# Card.net
KiCad netlist of a schematic drawn in EAGLE
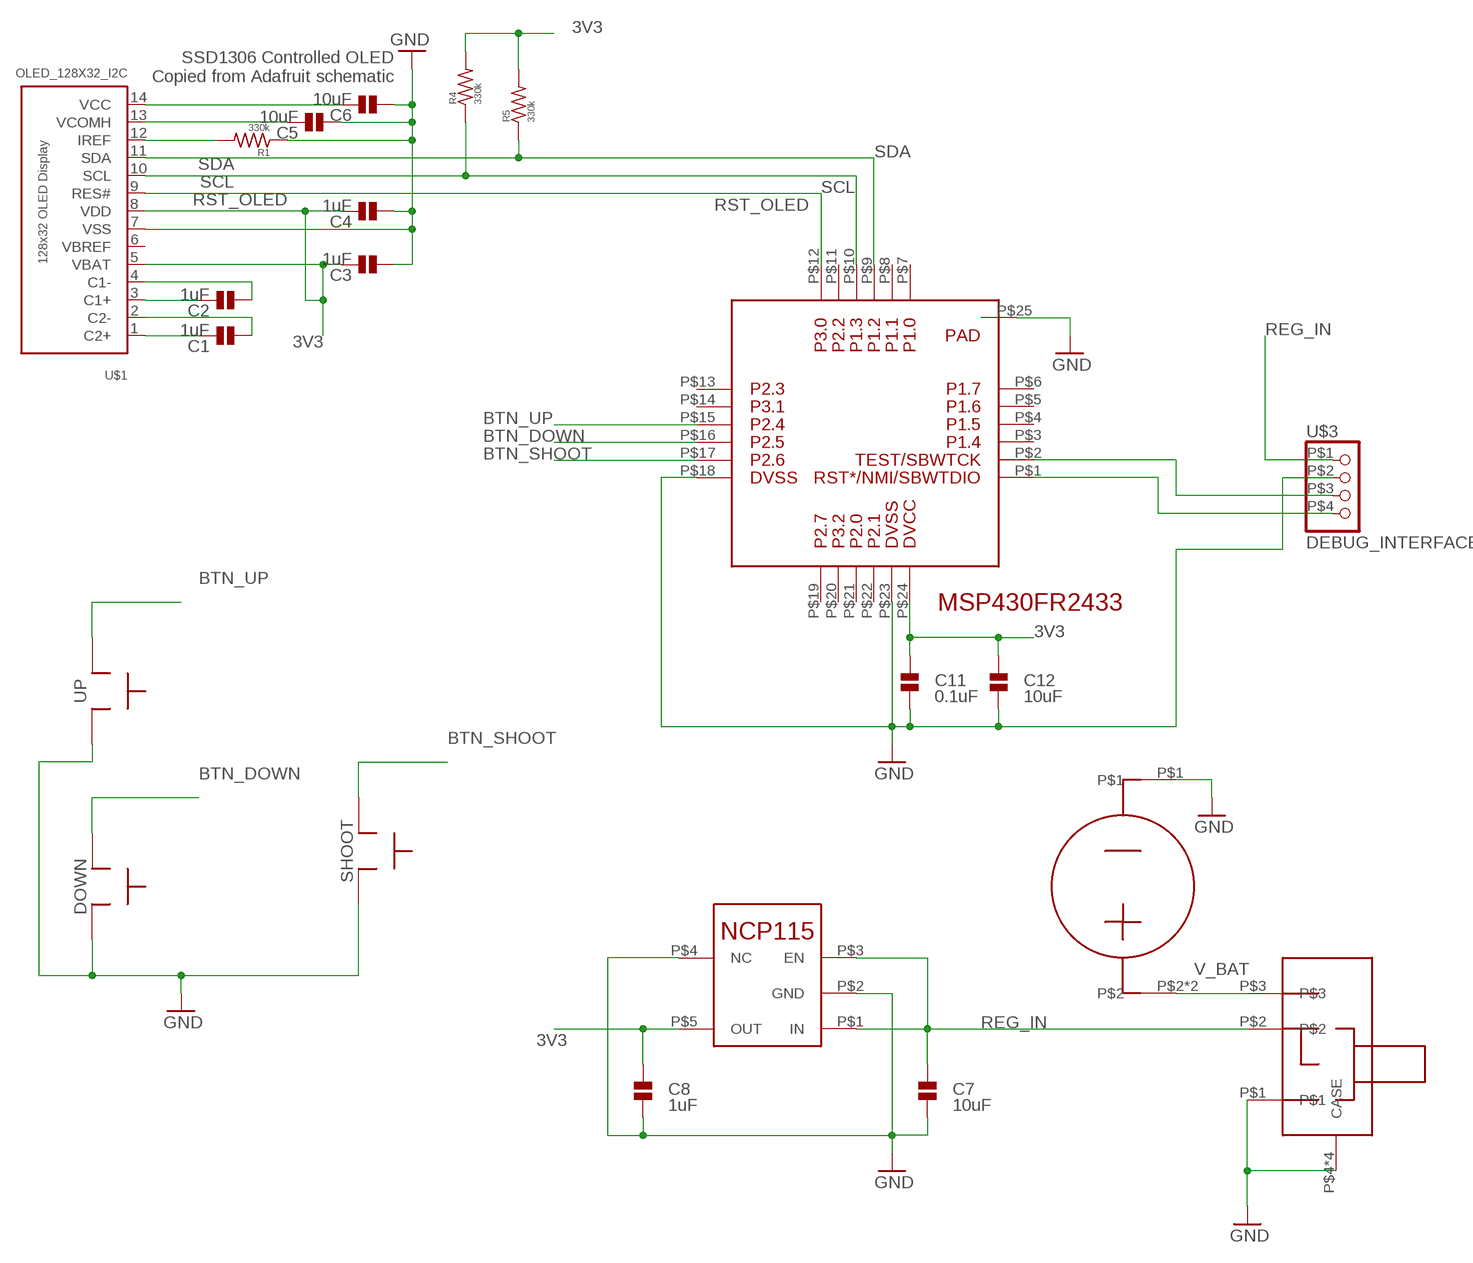
[diagram p0: schematic, sheet 1]

(export (version "E")
  (design (tool "Eeschema 10.0.6"))
  (components
    (comp (ref "C1")
      (value "1uF")
      (footprint "eagle-import:0603")
      (libsource (lib "eagle-import") (part "C-0603"))
    )
    (comp (ref "C2")
      (value "1uF")
      (footprint "eagle-import:0603")
      (libsource (lib "eagle-import") (part "C-0603"))
    )
    (comp (ref "C3")
      (value "1uF")
      (footprint "eagle-import:0603")
      (libsource (lib "eagle-import") (part "C-0603"))
    )
    (comp (ref "C4")
      (value "1uF")
      (footprint "eagle-import:0603")
      (libsource (lib "eagle-import") (part "C-0603"))
    )
    (comp (ref "C5")
      (value "10uF")
      (footprint "eagle-import:0603")
      (libsource (lib "eagle-import") (part "C-0603"))
    )
    (comp (ref "C6")
      (value "10uF")
      (footprint "eagle-import:0603")
      (libsource (lib "eagle-import") (part "C-0603"))
    )
    (comp (ref "C7")
      (value "10uF")
      (footprint "eagle-import:0603")
      (libsource (lib "eagle-import") (part "C-0603"))
    )
    (comp (ref "C8")
      (value "1uF")
      (footprint "eagle-import:0603")
      (libsource (lib "eagle-import") (part "C-0603"))
    )
    (comp (ref "C11")
      (value "0.1uF")
      (footprint "eagle-import:0603")
      (libsource (lib "eagle-import") (part "C-0603"))
    )
    (comp (ref "C12")
      (value "10uF")
      (footprint "eagle-import:0603")
      (libsource (lib "eagle-import") (part "C-0603"))
    )
    (comp (ref "DOWN")
      (value "EVQ-Q2B02W")
      (footprint "eagle-import:EVQQ2")
      (libsource (lib "eagle-import") (part "EVQ-Q2B02W"))
    )
    (comp (ref "R1")
      (value "330k")
      (footprint "eagle-import:0603")
      (libsource (lib "eagle-import") (part "R-0603"))
    )
    (comp (ref "R4")
      (value "330k")
      (footprint "eagle-import:0603")
      (libsource (lib "eagle-import") (part "R-0603"))
    )
    (comp (ref "R5")
      (value "330k")
      (footprint "eagle-import:0603")
      (libsource (lib "eagle-import") (part "R-0603"))
    )
    (comp (ref "SHOOT")
      (value "EVQ-Q2B02W")
      (footprint "eagle-import:EVQQ2")
      (libsource (lib "eagle-import") (part "EVQ-Q2B02W"))
    )
    (comp (ref "U$1")
      (value "OLED_128X32_I2C")
      (footprint "eagle-import:OLED_I2C")
      (libsource (lib "eagle-import") (part "OLED_128X32_I2C"))
    )
    (comp (ref "U$2")
      (value "MSP430FR2433-VQFN")
      (footprint "eagle-import:VQFN-24")
      (libsource (lib "eagle-import") (part "MSP430FR2433-VQFN"))
    )
    (comp (ref "U$3")
      (value "DEBUG_INTERFACE")
      (footprint "eagle-import:DEBUG_INTERFACE_6PIN")
      (libsource (lib "eagle-import") (part "DEBUG_INTERFACE"))
    )
    (comp (ref "U$4")
      (value "BAT-HLD-001")
      (footprint "eagle-import:BAT-HLD-001")
      (libsource (lib "eagle-import") (part "BAT-HLD-001"))
    )
    (comp (ref "U$5")
      (value "CUS-12TB")
      (footprint "eagle-import:CUS-12B")
      (libsource (lib "eagle-import") (part "CUS-12TB"))
    )
    (comp (ref "U$6")
      (value "NCP115")
      (footprint "eagle-import:TSOP-5")
      (libsource (lib "eagle-import") (part "NCP115"))
    )
    (comp (ref "UP")
      (value "EVQ-Q2B02W")
      (footprint "eagle-import:EVQQ2")
      (libsource (lib "eagle-import") (part "EVQ-Q2B02W"))
    )
  )
  (nets
    (net (code "1") (name "/3V3") (class "Default")
      (node (ref "C11") (pin "2") (pinfunction "2_2") (pintype "passive"))
      (node (ref "C12") (pin "2") (pinfunction "2_2") (pintype "passive"))
      (node (ref "C3") (pin "2") (pinfunction "2_2") (pintype "passive"))
      (node (ref "C4") (pin "2") (pinfunction "2_2") (pintype "passive"))
      (node (ref "C8") (pin "2") (pinfunction "2_2") (pintype "passive"))
      (node (ref "R4") (pin "2") (pinfunction "2_2") (pintype "passive"))
      (node (ref "R5") (pin "2") (pinfunction "2_2") (pintype "passive"))
      (node (ref "U$1") (pin "5") (pinfunction "VBAT_5") (pintype "power_in"))
      (node (ref "U$1") (pin "8") (pinfunction "VDD_8") (pintype "power_in"))
      (node (ref "U$2") (pin "P$24") (pinfunction "P$24_P$24") (pintype "bidirectional"))
      (node (ref "U$6") (pin "P$5") (pinfunction "OUT_P$5") (pintype "bidirectional"))
    )
    (net (code "2") (name "/BTN_DOWN") (class "Default")
      (node (ref "DOWN") (pin "P$1_A") (pinfunction "P$1_P$1_A") (pintype "bidirectional"))
      (node (ref "DOWN") (pin "P$2_A") (pinfunction "P$1_P$2_A") (pintype "bidirectional"))
      (node (ref "U$2") (pin "P$16") (pinfunction "P$16_P$16") (pintype "bidirectional"))
    )
    (net (code "3") (name "/BTN_SHOOT") (class "Default")
      (node (ref "SHOOT") (pin "P$1_A") (pinfunction "P$1_P$1_A") (pintype "bidirectional"))
      (node (ref "SHOOT") (pin "P$2_A") (pinfunction "P$1_P$2_A") (pintype "bidirectional"))
      (node (ref "U$2") (pin "P$17") (pinfunction "P$17_P$17") (pintype "bidirectional"))
    )
    (net (code "4") (name "/BTN_UP") (class "Default")
      (node (ref "U$2") (pin "P$15") (pinfunction "P$15_P$15") (pintype "bidirectional"))
      (node (ref "UP") (pin "P$1_A") (pinfunction "P$1_P$1_A") (pintype "bidirectional"))
      (node (ref "UP") (pin "P$2_A") (pinfunction "P$1_P$2_A") (pintype "bidirectional"))
    )
    (net (code "5") (name "/REG_IN") (class "Default")
      (node (ref "C7") (pin "2") (pinfunction "2_2") (pintype "passive"))
      (node (ref "U$3") (pin "P$1") (pinfunction "P$1_P$1") (pintype "passive"))
      (node (ref "U$5") (pin "P$2") (pinfunction "P$2_P$2") (pintype "bidirectional"))
      (node (ref "U$6") (pin "P$1") (pinfunction "IN_P$1") (pintype "bidirectional"))
      (node (ref "U$6") (pin "P$3") (pinfunction "EN_P$3") (pintype "bidirectional"))
    )
    (net (code "6") (name "/RST_OLED") (class "Default")
      (node (ref "U$1") (pin "9") (pinfunction "RES#_9") (pintype "bidirectional"))
      (node (ref "U$2") (pin "P$12") (pinfunction "P$12_P$12") (pintype "bidirectional"))
    )
    (net (code "7") (name "/SCL") (class "Default")
      (node (ref "R4") (pin "1") (pinfunction "1_1") (pintype "passive"))
      (node (ref "U$1") (pin "10") (pinfunction "SCL_10") (pintype "bidirectional"))
      (node (ref "U$2") (pin "P$10") (pinfunction "P$10_P$10") (pintype "bidirectional"))
    )
    (net (code "8") (name "/SDA") (class "Default")
      (node (ref "R5") (pin "1") (pinfunction "1_1") (pintype "passive"))
      (node (ref "U$1") (pin "11") (pinfunction "SDA_11") (pintype "bidirectional"))
      (node (ref "U$2") (pin "P$9") (pinfunction "P$9_P$9") (pintype "bidirectional"))
    )
    (net (code "9") (name "/VBREF") (class "Default")
      (node (ref "U$1") (pin "6") (pinfunction "VBREF_6") (pintype "power_in"))
    )
    (net (code "10") (name "/V_BAT") (class "Default")
      (node (ref "U$4") (pin "P$2") (pinfunction "P$2_P$2") (pintype "bidirectional"))
      (node (ref "U$4") (pin "P$3") (pinfunction "P$2_P$3") (pintype "bidirectional"))
      (node (ref "U$5") (pin "P$3") (pinfunction "P$3_P$3") (pintype "bidirectional"))
    )
    (net (code "11") (name "GND") (class "Default")
      (node (ref "C11") (pin "1") (pinfunction "1_1") (pintype "passive"))
      (node (ref "C12") (pin "1") (pinfunction "1_1") (pintype "passive"))
      (node (ref "C3") (pin "1") (pinfunction "1_1") (pintype "passive"))
      (node (ref "C4") (pin "1") (pinfunction "1_1") (pintype "passive"))
      (node (ref "C5") (pin "1") (pinfunction "1_1") (pintype "passive"))
      (node (ref "C6") (pin "1") (pinfunction "1_1") (pintype "passive"))
      (node (ref "C7") (pin "1") (pinfunction "1_1") (pintype "passive"))
      (node (ref "C8") (pin "1") (pinfunction "1_1") (pintype "passive"))
      (node (ref "DOWN") (pin "P$3_B") (pinfunction "P$2_P$3_B") (pintype "bidirectional"))
      (node (ref "DOWN") (pin "P$4_B") (pinfunction "P$2_P$4_B") (pintype "bidirectional"))
      (node (ref "R1") (pin "1") (pinfunction "1_1") (pintype "passive"))
      (node (ref "SHOOT") (pin "P$3_B") (pinfunction "P$2_P$3_B") (pintype "bidirectional"))
      (node (ref "SHOOT") (pin "P$4_B") (pinfunction "P$2_P$4_B") (pintype "bidirectional"))
      (node (ref "U$1") (pin "7") (pinfunction "VSS_7") (pintype "power_in"))
      (node (ref "U$2") (pin "P$18") (pinfunction "P$18_P$18") (pintype "bidirectional"))
      (node (ref "U$2") (pin "P$23") (pinfunction "P$23_P$23") (pintype "bidirectional"))
      (node (ref "U$2") (pin "P$25") (pinfunction "P$25_P$25") (pintype "bidirectional"))
      (node (ref "U$3") (pin "P$2") (pinfunction "P$2_P$2") (pintype "passive"))
      (node (ref "U$4") (pin "P$1") (pinfunction "P$1_P$1") (pintype "bidirectional"))
      (node (ref "U$5") (pin "P$1") (pinfunction "P$1_P$1") (pintype "bidirectional"))
      (node (ref "U$5") (pin "P$4") (pinfunction "CASE_P$4") (pintype "bidirectional"))
      (node (ref "U$5") (pin "P$5") (pinfunction "CASE_P$5") (pintype "bidirectional"))
      (node (ref "U$5") (pin "P$6") (pinfunction "CASE_P$6") (pintype "bidirectional"))
      (node (ref "U$5") (pin "P$7") (pinfunction "CASE_P$7") (pintype "bidirectional"))
      (node (ref "U$6") (pin "P$2") (pinfunction "GND_P$2") (pintype "bidirectional"))
      (node (ref "U$6") (pin "P$4") (pinfunction "NC_P$4") (pintype "bidirectional"))
      (node (ref "UP") (pin "P$3_B") (pinfunction "P$2_P$3_B") (pintype "bidirectional"))
      (node (ref "UP") (pin "P$4_B") (pinfunction "P$2_P$4_B") (pintype "bidirectional"))
    )
    (net (code "12") (name "Net-(U$1-C1+)") (class "Default")
      (node (ref "C2") (pin "2") (pinfunction "2_2") (pintype "passive"))
      (node (ref "U$1") (pin "3") (pinfunction "C1+_3") (pintype "bidirectional"))
    )
    (net (code "13") (name "Net-(U$1-C1-)") (class "Default")
      (node (ref "C2") (pin "1") (pinfunction "1_1") (pintype "passive"))
      (node (ref "U$1") (pin "4") (pinfunction "C1-_4") (pintype "bidirectional"))
    )
    (net (code "14") (name "Net-(U$1-C2+)") (class "Default")
      (node (ref "C1") (pin "2") (pinfunction "2_2") (pintype "passive"))
      (node (ref "U$1") (pin "1") (pinfunction "C2+_1") (pintype "bidirectional"))
    )
    (net (code "15") (name "Net-(U$1-C2-)") (class "Default")
      (node (ref "C1") (pin "1") (pinfunction "1_1") (pintype "passive"))
      (node (ref "U$1") (pin "2") (pinfunction "C2-_2") (pintype "bidirectional"))
    )
    (net (code "16") (name "Net-(U$1-IREF)") (class "Default")
      (node (ref "R1") (pin "2") (pinfunction "2_2") (pintype "passive"))
      (node (ref "U$1") (pin "12") (pinfunction "IREF_12") (pintype "bidirectional"))
    )
    (net (code "17") (name "Net-(U$1-VCC)") (class "Default")
      (node (ref "C6") (pin "2") (pinfunction "2_2") (pintype "passive"))
      (node (ref "U$1") (pin "14") (pinfunction "VCC_14") (pintype "power_in"))
    )
    (net (code "18") (name "Net-(U$1-VCOMH)") (class "Default")
      (node (ref "C5") (pin "2") (pinfunction "2_2") (pintype "passive"))
      (node (ref "U$1") (pin "13") (pinfunction "VCOMH_13") (pintype "power_in"))
    )
    (net (code "19") (name "Net-(U$2-PadP$1)") (class "Default")
      (node (ref "U$2") (pin "P$1") (pinfunction "P$1_P$1") (pintype "bidirectional"))
      (node (ref "U$3") (pin "P$4") (pinfunction "P$4_P$4") (pintype "passive"))
    )
    (net (code "20") (name "Net-(U$2-PadP$2)") (class "Default")
      (node (ref "U$2") (pin "P$2") (pinfunction "P$2_P$2") (pintype "bidirectional"))
      (node (ref "U$3") (pin "P$3") (pinfunction "P$3_P$3") (pintype "passive"))
    )
    (net (code "21") (name "unconnected-(U$2-PadP$3)") (class "Default")
      (node (ref "U$2") (pin "P$3") (pinfunction "P$3_P$3") (pintype "bidirectional"))
    )
    (net (code "22") (name "unconnected-(U$2-PadP$4)") (class "Default")
      (node (ref "U$2") (pin "P$4") (pinfunction "P$4_P$4") (pintype "bidirectional"))
    )
    (net (code "23") (name "unconnected-(U$2-PadP$5)") (class "Default")
      (node (ref "U$2") (pin "P$5") (pinfunction "P$5_P$5") (pintype "bidirectional"))
    )
    (net (code "24") (name "unconnected-(U$2-PadP$6)") (class "Default")
      (node (ref "U$2") (pin "P$6") (pinfunction "P$6_P$6") (pintype "bidirectional"))
    )
    (net (code "25") (name "unconnected-(U$2-PadP$7)") (class "Default")
      (node (ref "U$2") (pin "P$7") (pinfunction "P$7_P$7") (pintype "bidirectional"))
    )
    (net (code "26") (name "unconnected-(U$2-PadP$8)") (class "Default")
      (node (ref "U$2") (pin "P$8") (pinfunction "P$8_P$8") (pintype "bidirectional"))
    )
    (net (code "27") (name "unconnected-(U$2-PadP$11)") (class "Default")
      (node (ref "U$2") (pin "P$11") (pinfunction "P$11_P$11") (pintype "bidirectional"))
    )
    (net (code "28") (name "unconnected-(U$2-PadP$13)") (class "Default")
      (node (ref "U$2") (pin "P$13") (pinfunction "P$13_P$13") (pintype "bidirectional"))
    )
    (net (code "29") (name "unconnected-(U$2-PadP$14)") (class "Default")
      (node (ref "U$2") (pin "P$14") (pinfunction "P$14_P$14") (pintype "bidirectional"))
    )
    (net (code "30") (name "unconnected-(U$2-PadP$19)") (class "Default")
      (node (ref "U$2") (pin "P$19") (pinfunction "P$19_P$19") (pintype "bidirectional"))
    )
    (net (code "31") (name "unconnected-(U$2-PadP$20)") (class "Default")
      (node (ref "U$2") (pin "P$20") (pinfunction "P$20_P$20") (pintype "bidirectional"))
    )
    (net (code "32") (name "unconnected-(U$2-PadP$21)") (class "Default")
      (node (ref "U$2") (pin "P$21") (pinfunction "P$21_P$21") (pintype "bidirectional"))
    )
    (net (code "33") (name "unconnected-(U$2-PadP$22)") (class "Default")
      (node (ref "U$2") (pin "P$22") (pinfunction "P$22_P$22") (pintype "bidirectional"))
    )
  )
)
